# nanoscan.net
KiCad netlist of a schematic drawn in EAGLE
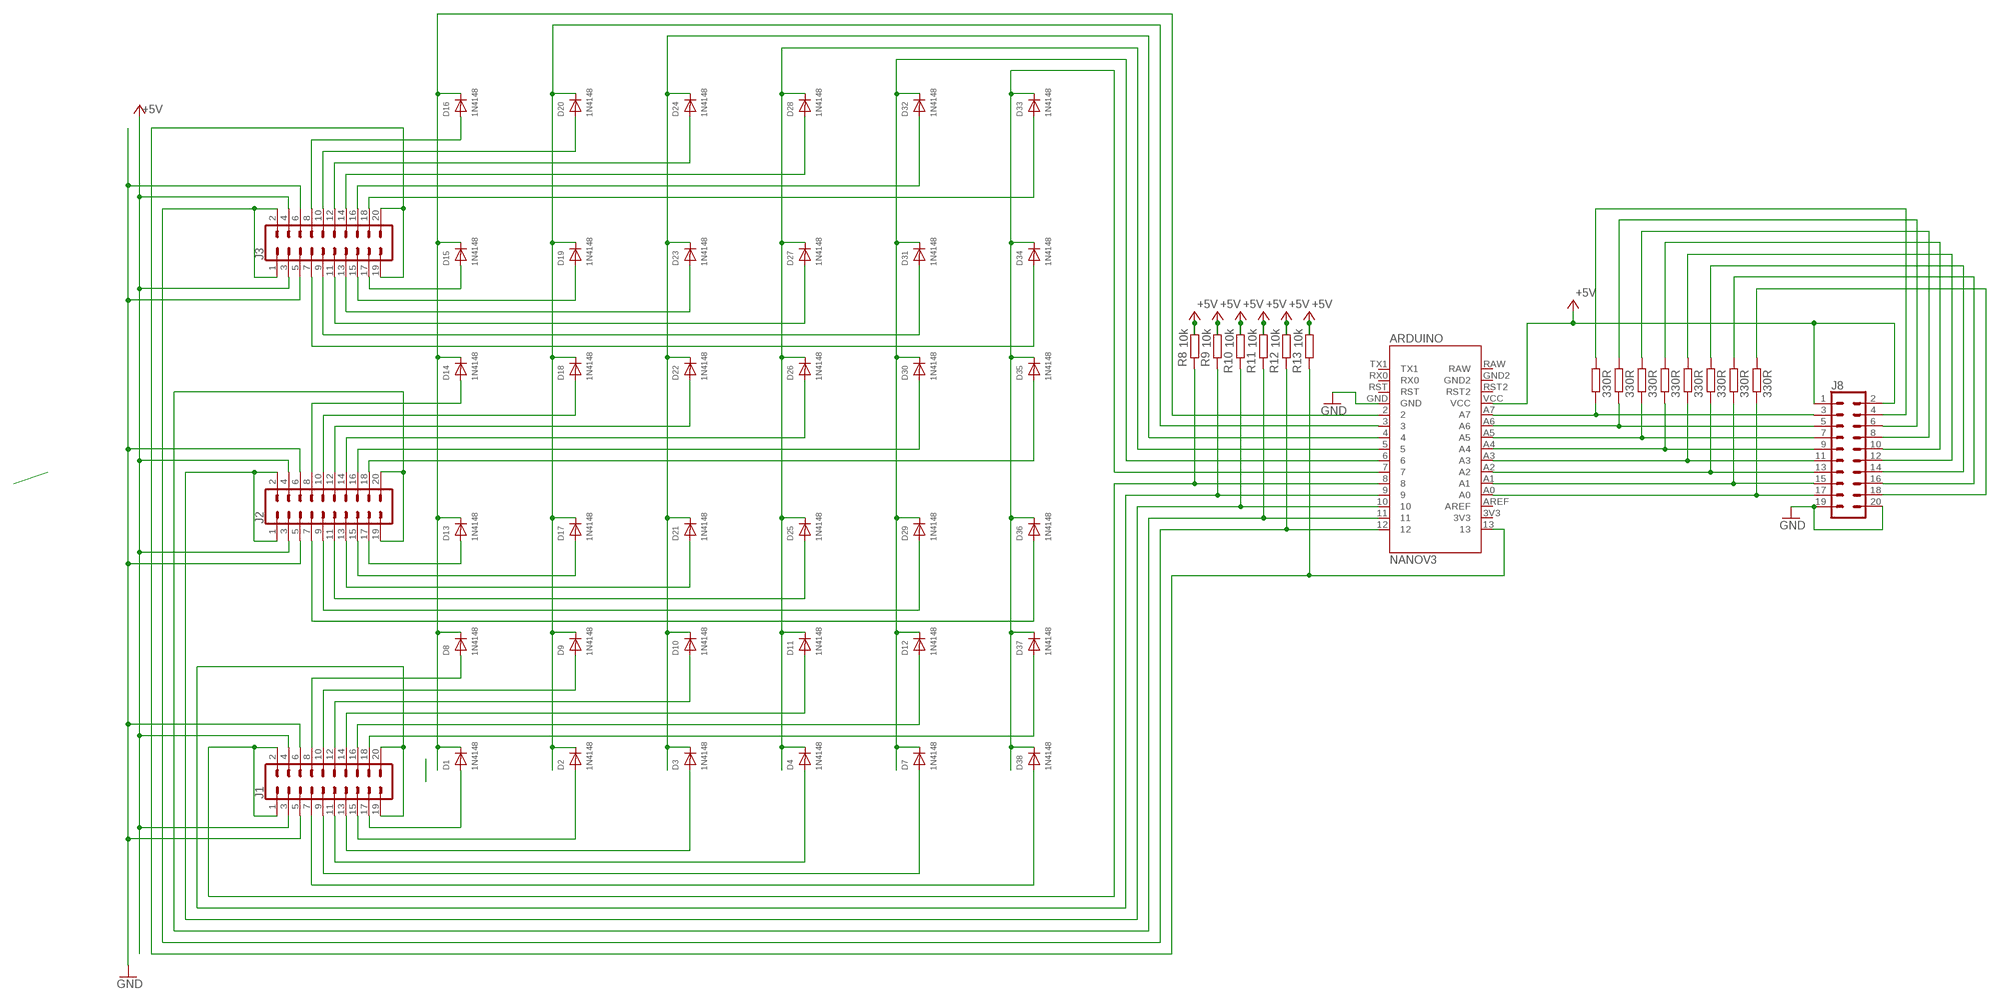
[diagram p0: schematic, sheet 1]

(export (version "E")
  (design (tool "Eeschema 10.0.6"))
  (components
    (comp (ref "ARDUINO")
      (value "NANOV3")
      (footprint "eagle-import:NANOV3")
      (libsource (lib "eagle-import") (part "NANOV3"))
    )
    (comp (ref "D1")
      (value "1N4148")
      (footprint "eagle-import:DO-1N4148")
      (libsource (lib "eagle-import") (part "DIODEDO-1N4148"))
    )
    (comp (ref "D2")
      (value "1N4148")
      (footprint "eagle-import:DO-1N4148")
      (libsource (lib "eagle-import") (part "DIODEDO-1N4148"))
    )
    (comp (ref "D3")
      (value "1N4148")
      (footprint "eagle-import:DO-1N4148")
      (libsource (lib "eagle-import") (part "DIODEDO-1N4148"))
    )
    (comp (ref "D4")
      (value "1N4148")
      (footprint "eagle-import:DO-1N4148")
      (libsource (lib "eagle-import") (part "DIODEDO-1N4148"))
    )
    (comp (ref "D7")
      (value "1N4148")
      (footprint "eagle-import:DO-1N4148")
      (libsource (lib "eagle-import") (part "DIODEDO-1N4148"))
    )
    (comp (ref "D8")
      (value "1N4148")
      (footprint "eagle-import:DO-1N4148")
      (libsource (lib "eagle-import") (part "DIODEDO-1N4148"))
    )
    (comp (ref "D9")
      (value "1N4148")
      (footprint "eagle-import:DO-1N4148")
      (libsource (lib "eagle-import") (part "DIODEDO-1N4148"))
    )
    (comp (ref "D10")
      (value "1N4148")
      (footprint "eagle-import:DO-1N4148")
      (libsource (lib "eagle-import") (part "DIODEDO-1N4148"))
    )
    (comp (ref "D11")
      (value "1N4148")
      (footprint "eagle-import:DO-1N4148")
      (libsource (lib "eagle-import") (part "DIODEDO-1N4148"))
    )
    (comp (ref "D12")
      (value "1N4148")
      (footprint "eagle-import:DO-1N4148")
      (libsource (lib "eagle-import") (part "DIODEDO-1N4148"))
    )
    (comp (ref "D13")
      (value "1N4148")
      (footprint "eagle-import:DO-1N4148")
      (libsource (lib "eagle-import") (part "DIODEDO-1N4148"))
    )
    (comp (ref "D14")
      (value "1N4148")
      (footprint "eagle-import:DO-1N4148")
      (libsource (lib "eagle-import") (part "DIODEDO-1N4148"))
    )
    (comp (ref "D15")
      (value "1N4148")
      (footprint "eagle-import:DO-1N4148")
      (libsource (lib "eagle-import") (part "DIODEDO-1N4148"))
    )
    (comp (ref "D16")
      (value "1N4148")
      (footprint "eagle-import:DO-1N4148")
      (libsource (lib "eagle-import") (part "DIODEDO-1N4148"))
    )
    (comp (ref "D17")
      (value "1N4148")
      (footprint "eagle-import:DO-1N4148")
      (libsource (lib "eagle-import") (part "DIODEDO-1N4148"))
    )
    (comp (ref "D18")
      (value "1N4148")
      (footprint "eagle-import:DO-1N4148")
      (libsource (lib "eagle-import") (part "DIODEDO-1N4148"))
    )
    (comp (ref "D19")
      (value "1N4148")
      (footprint "eagle-import:DO-1N4148")
      (libsource (lib "eagle-import") (part "DIODEDO-1N4148"))
    )
    (comp (ref "D20")
      (value "1N4148")
      (footprint "eagle-import:DO-1N4148")
      (libsource (lib "eagle-import") (part "DIODEDO-1N4148"))
    )
    (comp (ref "D21")
      (value "1N4148")
      (footprint "eagle-import:DO-1N4148")
      (libsource (lib "eagle-import") (part "DIODEDO-1N4148"))
    )
    (comp (ref "D22")
      (value "1N4148")
      (footprint "eagle-import:DO-1N4148")
      (libsource (lib "eagle-import") (part "DIODEDO-1N4148"))
    )
    (comp (ref "D23")
      (value "1N4148")
      (footprint "eagle-import:DO-1N4148")
      (libsource (lib "eagle-import") (part "DIODEDO-1N4148"))
    )
    (comp (ref "D24")
      (value "1N4148")
      (footprint "eagle-import:DO-1N4148")
      (libsource (lib "eagle-import") (part "DIODEDO-1N4148"))
    )
    (comp (ref "D25")
      (value "1N4148")
      (footprint "eagle-import:DO-1N4148")
      (libsource (lib "eagle-import") (part "DIODEDO-1N4148"))
    )
    (comp (ref "D26")
      (value "1N4148")
      (footprint "eagle-import:DO-1N4148")
      (libsource (lib "eagle-import") (part "DIODEDO-1N4148"))
    )
    (comp (ref "D27")
      (value "1N4148")
      (footprint "eagle-import:DO-1N4148")
      (libsource (lib "eagle-import") (part "DIODEDO-1N4148"))
    )
    (comp (ref "D28")
      (value "1N4148")
      (footprint "eagle-import:DO-1N4148")
      (libsource (lib "eagle-import") (part "DIODEDO-1N4148"))
    )
    (comp (ref "D29")
      (value "1N4148")
      (footprint "eagle-import:DO-1N4148")
      (libsource (lib "eagle-import") (part "DIODEDO-1N4148"))
    )
    (comp (ref "D30")
      (value "1N4148")
      (footprint "eagle-import:DO-1N4148")
      (libsource (lib "eagle-import") (part "DIODEDO-1N4148"))
    )
    (comp (ref "D31")
      (value "1N4148")
      (footprint "eagle-import:DO-1N4148")
      (libsource (lib "eagle-import") (part "DIODEDO-1N4148"))
    )
    (comp (ref "D32")
      (value "1N4148")
      (footprint "eagle-import:DO-1N4148")
      (libsource (lib "eagle-import") (part "DIODEDO-1N4148"))
    )
    (comp (ref "D33")
      (value "1N4148")
      (footprint "eagle-import:DO-1N4148")
      (libsource (lib "eagle-import") (part "DIODEDO-1N4148"))
    )
    (comp (ref "D34")
      (value "1N4148")
      (footprint "eagle-import:DO-1N4148")
      (libsource (lib "eagle-import") (part "DIODEDO-1N4148"))
    )
    (comp (ref "D35")
      (value "1N4148")
      (footprint "eagle-import:DO-1N4148")
      (libsource (lib "eagle-import") (part "DIODEDO-1N4148"))
    )
    (comp (ref "D36")
      (value "1N4148")
      (footprint "eagle-import:DO-1N4148")
      (libsource (lib "eagle-import") (part "DIODEDO-1N4148"))
    )
    (comp (ref "D37")
      (value "1N4148")
      (footprint "eagle-import:DO-1N4148")
      (libsource (lib "eagle-import") (part "DIODEDO-1N4148"))
    )
    (comp (ref "D38")
      (value "1N4148")
      (footprint "eagle-import:DO-1N4148")
      (libsource (lib "eagle-import") (part "DIODEDO-1N4148"))
    )
    (comp (ref "J1")
      (value "CONN_10X2SPECIAL")
      (footprint "eagle-import:2X10_LOCK_SPECIAL")
      (libsource (lib "eagle-import") (part "CONN_10X2SPECIAL"))
    )
    (comp (ref "J2")
      (value "CONN_10X2SPECIAL")
      (footprint "eagle-import:2X10_LOCK_SPECIAL")
      (libsource (lib "eagle-import") (part "CONN_10X2SPECIAL"))
    )
    (comp (ref "J3")
      (value "CONN_10X2SPECIAL")
      (footprint "eagle-import:2X10_LOCK_SPECIAL")
      (libsource (lib "eagle-import") (part "CONN_10X2SPECIAL"))
    )
    (comp (ref "J8")
      (value "CONN_10X2SPECIAL")
      (footprint "eagle-import:2X10_LOCK_SPECIAL")
      (libsource (lib "eagle-import") (part "CONN_10X2SPECIAL"))
    )
    (comp (ref "R0")
      (value "330R")
      (footprint "eagle-import:0207_10")
      (libsource (lib "eagle-import") (part "R-EU_0207/10"))
    )
    (comp (ref "R1")
      (value "330R")
      (footprint "eagle-import:0207_10")
      (libsource (lib "eagle-import") (part "R-EU_0207/10"))
    )
    (comp (ref "R2")
      (value "330R")
      (footprint "eagle-import:0207_10")
      (libsource (lib "eagle-import") (part "R-EU_0207/10"))
    )
    (comp (ref "R3")
      (value "330R")
      (footprint "eagle-import:0207_10")
      (libsource (lib "eagle-import") (part "R-EU_0207/10"))
    )
    (comp (ref "R4")
      (value "330R")
      (footprint "eagle-import:0207_10")
      (libsource (lib "eagle-import") (part "R-EU_0207/10"))
    )
    (comp (ref "R5")
      (value "330R")
      (footprint "eagle-import:0207_10")
      (libsource (lib "eagle-import") (part "R-EU_0207/10"))
    )
    (comp (ref "R6")
      (value "330R")
      (footprint "eagle-import:0207_10")
      (libsource (lib "eagle-import") (part "R-EU_0207/10"))
    )
    (comp (ref "R7")
      (value "330R")
      (footprint "eagle-import:0207_10")
      (libsource (lib "eagle-import") (part "R-EU_0207/10"))
    )
    (comp (ref "R8")
      (value "10k")
      (footprint "eagle-import:0207_10")
      (libsource (lib "eagle-import") (part "R-EU_0207/10"))
    )
    (comp (ref "R9")
      (value "10k")
      (footprint "eagle-import:0207_10")
      (libsource (lib "eagle-import") (part "R-EU_0207/10"))
    )
    (comp (ref "R10")
      (value "10k")
      (footprint "eagle-import:0207_10")
      (libsource (lib "eagle-import") (part "R-EU_0207/10"))
    )
    (comp (ref "R11")
      (value "10k")
      (footprint "eagle-import:0207_10")
      (libsource (lib "eagle-import") (part "R-EU_0207/10"))
    )
    (comp (ref "R12")
      (value "10k")
      (footprint "eagle-import:0207_10")
      (libsource (lib "eagle-import") (part "R-EU_0207/10"))
    )
    (comp (ref "R13")
      (value "10k")
      (footprint "eagle-import:0207_10")
      (libsource (lib "eagle-import") (part "R-EU_0207/10"))
    )
  )
  (nets
    (net (code "1") (name "+5V") (class "Default")
      (node (ref "ARDUINO") (pin "VCC") (pinfunction "VCC_VCC") (pintype "bidirectional"))
      (node (ref "J1") (pin "3") (pinfunction "3_3") (pintype "passive"))
      (node (ref "J1") (pin "4") (pinfunction "4_4") (pintype "passive"))
      (node (ref "J2") (pin "3") (pinfunction "3_3") (pintype "passive"))
      (node (ref "J2") (pin "4") (pinfunction "4_4") (pintype "passive"))
      (node (ref "J3") (pin "3") (pinfunction "3_3") (pintype "passive"))
      (node (ref "J3") (pin "4") (pinfunction "4_4") (pintype "passive"))
      (node (ref "J8") (pin "1") (pinfunction "1_1") (pintype "passive"))
      (node (ref "J8") (pin "2") (pinfunction "2_2") (pintype "passive"))
      (node (ref "R10") (pin "1") (pinfunction "1_1") (pintype "passive"))
      (node (ref "R11") (pin "1") (pinfunction "1_1") (pintype "passive"))
      (node (ref "R12") (pin "1") (pinfunction "1_1") (pintype "passive"))
      (node (ref "R13") (pin "1") (pinfunction "1_1") (pintype "passive"))
      (node (ref "R8") (pin "1") (pinfunction "1_1") (pintype "passive"))
      (node (ref "R9") (pin "1") (pinfunction "1_1") (pintype "passive"))
    )
    (net (code "2") (name "GND") (class "Default")
      (node (ref "ARDUINO") (pin "GND") (pinfunction "GND_GND") (pintype "bidirectional"))
      (node (ref "J1") (pin "5") (pinfunction "5_5") (pintype "passive"))
      (node (ref "J1") (pin "6") (pinfunction "6_6") (pintype "passive"))
      (node (ref "J2") (pin "5") (pinfunction "5_5") (pintype "passive"))
      (node (ref "J2") (pin "6") (pinfunction "6_6") (pintype "passive"))
      (node (ref "J3") (pin "5") (pinfunction "5_5") (pintype "passive"))
      (node (ref "J3") (pin "6") (pinfunction "6_6") (pintype "passive"))
      (node (ref "J8") (pin "19") (pinfunction "19_19") (pintype "passive"))
      (node (ref "J8") (pin "20") (pinfunction "20_20") (pintype "passive"))
    )
    (net (code "3") (name "Net-(ARDUINO-Pad2)") (class "Default")
      (node (ref "ARDUINO") (pin "2") (pinfunction "2_2") (pintype "bidirectional"))
      (node (ref "D1") (pin "C") (pinfunction "C_C") (pintype "passive"))
      (node (ref "D13") (pin "C") (pinfunction "C_C") (pintype "passive"))
      (node (ref "D14") (pin "C") (pinfunction "C_C") (pintype "passive"))
      (node (ref "D15") (pin "C") (pinfunction "C_C") (pintype "passive"))
      (node (ref "D16") (pin "C") (pinfunction "C_C") (pintype "passive"))
      (node (ref "D8") (pin "C") (pinfunction "C_C") (pintype "passive"))
    )
    (net (code "4") (name "Net-(ARDUINO-Pad3)") (class "Default")
      (node (ref "ARDUINO") (pin "3") (pinfunction "3_3") (pintype "bidirectional"))
      (node (ref "D17") (pin "C") (pinfunction "C_C") (pintype "passive"))
      (node (ref "D18") (pin "C") (pinfunction "C_C") (pintype "passive"))
      (node (ref "D19") (pin "C") (pinfunction "C_C") (pintype "passive"))
      (node (ref "D2") (pin "C") (pinfunction "C_C") (pintype "passive"))
      (node (ref "D20") (pin "C") (pinfunction "C_C") (pintype "passive"))
      (node (ref "D9") (pin "C") (pinfunction "C_C") (pintype "passive"))
    )
    (net (code "5") (name "Net-(ARDUINO-Pad4)") (class "Default")
      (node (ref "ARDUINO") (pin "4") (pinfunction "4_4") (pintype "bidirectional"))
      (node (ref "D10") (pin "C") (pinfunction "C_C") (pintype "passive"))
      (node (ref "D21") (pin "C") (pinfunction "C_C") (pintype "passive"))
      (node (ref "D22") (pin "C") (pinfunction "C_C") (pintype "passive"))
      (node (ref "D23") (pin "C") (pinfunction "C_C") (pintype "passive"))
      (node (ref "D24") (pin "C") (pinfunction "C_C") (pintype "passive"))
      (node (ref "D3") (pin "C") (pinfunction "C_C") (pintype "passive"))
    )
    (net (code "6") (name "Net-(ARDUINO-Pad5)") (class "Default")
      (node (ref "ARDUINO") (pin "5") (pinfunction "5_5") (pintype "bidirectional"))
      (node (ref "D11") (pin "C") (pinfunction "C_C") (pintype "passive"))
      (node (ref "D25") (pin "C") (pinfunction "C_C") (pintype "passive"))
      (node (ref "D26") (pin "C") (pinfunction "C_C") (pintype "passive"))
      (node (ref "D27") (pin "C") (pinfunction "C_C") (pintype "passive"))
      (node (ref "D28") (pin "C") (pinfunction "C_C") (pintype "passive"))
      (node (ref "D4") (pin "C") (pinfunction "C_C") (pintype "passive"))
    )
    (net (code "7") (name "Net-(ARDUINO-Pad6)") (class "Default")
      (node (ref "ARDUINO") (pin "6") (pinfunction "6_6") (pintype "bidirectional"))
      (node (ref "D12") (pin "C") (pinfunction "C_C") (pintype "passive"))
      (node (ref "D29") (pin "C") (pinfunction "C_C") (pintype "passive"))
      (node (ref "D30") (pin "C") (pinfunction "C_C") (pintype "passive"))
      (node (ref "D31") (pin "C") (pinfunction "C_C") (pintype "passive"))
      (node (ref "D32") (pin "C") (pinfunction "C_C") (pintype "passive"))
      (node (ref "D7") (pin "C") (pinfunction "C_C") (pintype "passive"))
    )
    (net (code "8") (name "Net-(ARDUINO-Pad7)") (class "Default")
      (node (ref "ARDUINO") (pin "7") (pinfunction "7_7") (pintype "bidirectional"))
      (node (ref "D33") (pin "C") (pinfunction "C_C") (pintype "passive"))
      (node (ref "D34") (pin "C") (pinfunction "C_C") (pintype "passive"))
      (node (ref "D35") (pin "C") (pinfunction "C_C") (pintype "passive"))
      (node (ref "D36") (pin "C") (pinfunction "C_C") (pintype "passive"))
      (node (ref "D37") (pin "C") (pinfunction "C_C") (pintype "passive"))
      (node (ref "D38") (pin "C") (pinfunction "C_C") (pintype "passive"))
    )
    (net (code "9") (name "Net-(ARDUINO-Pad8)") (class "Default")
      (node (ref "ARDUINO") (pin "8") (pinfunction "8_8") (pintype "bidirectional"))
      (node (ref "J1") (pin "1") (pinfunction "1_1") (pintype "passive"))
      (node (ref "J1") (pin "2") (pinfunction "2_2") (pintype "passive"))
      (node (ref "R8") (pin "2") (pinfunction "2_2") (pintype "passive"))
    )
    (net (code "10") (name "Net-(ARDUINO-Pad9)") (class "Default")
      (node (ref "ARDUINO") (pin "9") (pinfunction "9_9") (pintype "bidirectional"))
      (node (ref "J1") (pin "19") (pinfunction "19_19") (pintype "passive"))
      (node (ref "J1") (pin "20") (pinfunction "20_20") (pintype "passive"))
      (node (ref "R9") (pin "2") (pinfunction "2_2") (pintype "passive"))
    )
    (net (code "11") (name "Net-(ARDUINO-Pad10)") (class "Default")
      (node (ref "ARDUINO") (pin "10") (pinfunction "10_10") (pintype "bidirectional"))
      (node (ref "J2") (pin "1") (pinfunction "1_1") (pintype "passive"))
      (node (ref "J2") (pin "2") (pinfunction "2_2") (pintype "passive"))
      (node (ref "R10") (pin "2") (pinfunction "2_2") (pintype "passive"))
    )
    (net (code "12") (name "Net-(ARDUINO-Pad11)") (class "Default")
      (node (ref "ARDUINO") (pin "11") (pinfunction "11_11") (pintype "bidirectional"))
      (node (ref "J2") (pin "19") (pinfunction "19_19") (pintype "passive"))
      (node (ref "J2") (pin "20") (pinfunction "20_20") (pintype "passive"))
      (node (ref "R11") (pin "2") (pinfunction "2_2") (pintype "passive"))
    )
    (net (code "13") (name "Net-(ARDUINO-Pad12)") (class "Default")
      (node (ref "ARDUINO") (pin "12") (pinfunction "12_12") (pintype "bidirectional"))
      (node (ref "J3") (pin "1") (pinfunction "1_1") (pintype "passive"))
      (node (ref "J3") (pin "2") (pinfunction "2_2") (pintype "passive"))
      (node (ref "R12") (pin "2") (pinfunction "2_2") (pintype "passive"))
    )
    (net (code "14") (name "Net-(ARDUINO-Pad13)") (class "Default")
      (node (ref "ARDUINO") (pin "13") (pinfunction "13_13") (pintype "bidirectional"))
      (node (ref "J3") (pin "19") (pinfunction "19_19") (pintype "passive"))
      (node (ref "J3") (pin "20") (pinfunction "20_20") (pintype "passive"))
      (node (ref "R13") (pin "2") (pinfunction "2_2") (pintype "passive"))
    )
    (net (code "15") (name "Net-(ARDUINO-PadA0)") (class "Default")
      (node (ref "ARDUINO") (pin "A0") (pinfunction "A0_A0") (pintype "bidirectional"))
      (node (ref "J8") (pin "17") (pinfunction "17_17") (pintype "passive"))
      (node (ref "R0") (pin "1") (pinfunction "1_1") (pintype "passive"))
    )
    (net (code "16") (name "Net-(ARDUINO-PadA1)") (class "Default")
      (node (ref "ARDUINO") (pin "A1") (pinfunction "A1_A1") (pintype "bidirectional"))
      (node (ref "J8") (pin "15") (pinfunction "15_15") (pintype "passive"))
      (node (ref "R1") (pin "1") (pinfunction "1_1") (pintype "passive"))
    )
    (net (code "17") (name "Net-(ARDUINO-PadA2)") (class "Default")
      (node (ref "ARDUINO") (pin "A2") (pinfunction "A2_A2") (pintype "bidirectional"))
      (node (ref "J8") (pin "13") (pinfunction "13_13") (pintype "passive"))
      (node (ref "R2") (pin "1") (pinfunction "1_1") (pintype "passive"))
    )
    (net (code "18") (name "Net-(ARDUINO-PadA3)") (class "Default")
      (node (ref "ARDUINO") (pin "A3") (pinfunction "A3_A3") (pintype "bidirectional"))
      (node (ref "J8") (pin "11") (pinfunction "11_11") (pintype "passive"))
      (node (ref "R3") (pin "1") (pinfunction "1_1") (pintype "passive"))
    )
    (net (code "19") (name "Net-(ARDUINO-PadA4)") (class "Default")
      (node (ref "ARDUINO") (pin "A4") (pinfunction "A4_A4") (pintype "bidirectional"))
      (node (ref "J8") (pin "9") (pinfunction "9_9") (pintype "passive"))
      (node (ref "R4") (pin "1") (pinfunction "1_1") (pintype "passive"))
    )
    (net (code "20") (name "Net-(ARDUINO-PadA5)") (class "Default")
      (node (ref "ARDUINO") (pin "A5") (pinfunction "A5_A5") (pintype "bidirectional"))
      (node (ref "J8") (pin "7") (pinfunction "7_7") (pintype "passive"))
      (node (ref "R5") (pin "1") (pinfunction "1_1") (pintype "passive"))
    )
    (net (code "21") (name "Net-(ARDUINO-PadA6)") (class "Default")
      (node (ref "ARDUINO") (pin "A6") (pinfunction "A6_A6") (pintype "bidirectional"))
      (node (ref "J8") (pin "5") (pinfunction "5_5") (pintype "passive"))
      (node (ref "R6") (pin "1") (pinfunction "1_1") (pintype "passive"))
    )
    (net (code "22") (name "Net-(ARDUINO-PadA7)") (class "Default")
      (node (ref "ARDUINO") (pin "A7") (pinfunction "A7_A7") (pintype "bidirectional"))
      (node (ref "J8") (pin "3") (pinfunction "3_3") (pintype "passive"))
      (node (ref "R7") (pin "1") (pinfunction "1_1") (pintype "passive"))
    )
    (net (code "23") (name "Net-(D1-PadA)") (class "Default")
      (node (ref "D1") (pin "A") (pinfunction "A_A") (pintype "passive"))
      (node (ref "J1") (pin "17") (pinfunction "17_17") (pintype "passive"))
    )
    (net (code "24") (name "Net-(D2-PadA)") (class "Default")
      (node (ref "D2") (pin "A") (pinfunction "A_A") (pintype "passive"))
      (node (ref "J1") (pin "15") (pinfunction "15_15") (pintype "passive"))
    )
    (net (code "25") (name "Net-(D3-PadA)") (class "Default")
      (node (ref "D3") (pin "A") (pinfunction "A_A") (pintype "passive"))
      (node (ref "J1") (pin "13") (pinfunction "13_13") (pintype "passive"))
    )
    (net (code "26") (name "Net-(D4-PadA)") (class "Default")
      (node (ref "D4") (pin "A") (pinfunction "A_A") (pintype "passive"))
      (node (ref "J1") (pin "11") (pinfunction "11_11") (pintype "passive"))
    )
    (net (code "27") (name "Net-(D7-PadA)") (class "Default")
      (node (ref "D7") (pin "A") (pinfunction "A_A") (pintype "passive"))
      (node (ref "J1") (pin "9") (pinfunction "9_9") (pintype "passive"))
    )
    (net (code "28") (name "Net-(D8-PadA)") (class "Default")
      (node (ref "D8") (pin "A") (pinfunction "A_A") (pintype "passive"))
      (node (ref "J1") (pin "8") (pinfunction "8_8") (pintype "passive"))
    )
    (net (code "29") (name "Net-(D9-PadA)") (class "Default")
      (node (ref "D9") (pin "A") (pinfunction "A_A") (pintype "passive"))
      (node (ref "J1") (pin "10") (pinfunction "10_10") (pintype "passive"))
    )
    (net (code "30") (name "Net-(D10-PadA)") (class "Default")
      (node (ref "D10") (pin "A") (pinfunction "A_A") (pintype "passive"))
      (node (ref "J1") (pin "12") (pinfunction "12_12") (pintype "passive"))
    )
    (net (code "31") (name "Net-(D11-PadA)") (class "Default")
      (node (ref "D11") (pin "A") (pinfunction "A_A") (pintype "passive"))
      (node (ref "J1") (pin "14") (pinfunction "14_14") (pintype "passive"))
    )
    (net (code "32") (name "Net-(D12-PadA)") (class "Default")
      (node (ref "D12") (pin "A") (pinfunction "A_A") (pintype "passive"))
      (node (ref "J1") (pin "16") (pinfunction "16_16") (pintype "passive"))
    )
    (net (code "33") (name "Net-(D13-PadA)") (class "Default")
      (node (ref "D13") (pin "A") (pinfunction "A_A") (pintype "passive"))
      (node (ref "J2") (pin "17") (pinfunction "17_17") (pintype "passive"))
    )
    (net (code "34") (name "Net-(D14-PadA)") (class "Default")
      (node (ref "D14") (pin "A") (pinfunction "A_A") (pintype "passive"))
      (node (ref "J2") (pin "8") (pinfunction "8_8") (pintype "passive"))
    )
    (net (code "35") (name "Net-(D15-PadA)") (class "Default")
      (node (ref "D15") (pin "A") (pinfunction "A_A") (pintype "passive"))
      (node (ref "J3") (pin "17") (pinfunction "17_17") (pintype "passive"))
    )
    (net (code "36") (name "Net-(D16-PadA)") (class "Default")
      (node (ref "D16") (pin "A") (pinfunction "A_A") (pintype "passive"))
      (node (ref "J3") (pin "8") (pinfunction "8_8") (pintype "passive"))
    )
    (net (code "37") (name "Net-(D17-PadA)") (class "Default")
      (node (ref "D17") (pin "A") (pinfunction "A_A") (pintype "passive"))
      (node (ref "J2") (pin "15") (pinfunction "15_15") (pintype "passive"))
    )
    (net (code "38") (name "Net-(D18-PadA)") (class "Default")
      (node (ref "D18") (pin "A") (pinfunction "A_A") (pintype "passive"))
      (node (ref "J2") (pin "10") (pinfunction "10_10") (pintype "passive"))
    )
    (net (code "39") (name "Net-(D19-PadA)") (class "Default")
      (node (ref "D19") (pin "A") (pinfunction "A_A") (pintype "passive"))
      (node (ref "J3") (pin "15") (pinfunction "15_15") (pintype "passive"))
    )
    (net (code "40") (name "Net-(D20-PadA)") (class "Default")
      (node (ref "D20") (pin "A") (pinfunction "A_A") (pintype "passive"))
      (node (ref "J3") (pin "10") (pinfunction "10_10") (pintype "passive"))
    )
    (net (code "41") (name "Net-(D21-PadA)") (class "Default")
      (node (ref "D21") (pin "A") (pinfunction "A_A") (pintype "passive"))
      (node (ref "J2") (pin "13") (pinfunction "13_13") (pintype "passive"))
    )
    (net (code "42") (name "Net-(D22-PadA)") (class "Default")
      (node (ref "D22") (pin "A") (pinfunction "A_A") (pintype "passive"))
      (node (ref "J2") (pin "12") (pinfunction "12_12") (pintype "passive"))
    )
    (net (code "43") (name "Net-(D23-PadA)") (class "Default")
      (node (ref "D23") (pin "A") (pinfunction "A_A") (pintype "passive"))
      (node (ref "J3") (pin "13") (pinfunction "13_13") (pintype "passive"))
    )
    (net (code "44") (name "Net-(D24-PadA)") (class "Default")
      (node (ref "D24") (pin "A") (pinfunction "A_A") (pintype "passive"))
      (node (ref "J3") (pin "12") (pinfunction "12_12") (pintype "passive"))
    )
    (net (code "45") (name "Net-(D25-PadA)") (class "Default")
      (node (ref "D25") (pin "A") (pinfunction "A_A") (pintype "passive"))
      (node (ref "J2") (pin "11") (pinfunction "11_11") (pintype "passive"))
    )
    (net (code "46") (name "Net-(D26-PadA)") (class "Default")
      (node (ref "D26") (pin "A") (pinfunction "A_A") (pintype "passive"))
      (node (ref "J2") (pin "14") (pinfunction "14_14") (pintype "passive"))
    )
    (net (code "47") (name "Net-(D27-PadA)") (class "Default")
      (node (ref "D27") (pin "A") (pinfunction "A_A") (pintype "passive"))
      (node (ref "J3") (pin "11") (pinfunction "11_11") (pintype "passive"))
    )
    (net (code "48") (name "Net-(D28-PadA)") (class "Default")
      (node (ref "D28") (pin "A") (pinfunction "A_A") (pintype "passive"))
      (node (ref "J3") (pin "14") (pinfunction "14_14") (pintype "passive"))
    )
    (net (code "49") (name "Net-(D29-PadA)") (class "Default")
      (node (ref "D29") (pin "A") (pinfunction "A_A") (pintype "passive"))
      (node (ref "J2") (pin "9") (pinfunction "9_9") (pintype "passive"))
    )
    (net (code "50") (name "Net-(D30-PadA)") (class "Default")
      (node (ref "D30") (pin "A") (pinfunction "A_A") (pintype "passive"))
      (node (ref "J2") (pin "16") (pinfunction "16_16") (pintype "passive"))
    )
    (net (code "51") (name "Net-(D31-PadA)") (class "Default")
      (node (ref "D31") (pin "A") (pinfunction "A_A") (pintype "passive"))
      (node (ref "J3") (pin "9") (pinfunction "9_9") (pintype "passive"))
    )
    (net (code "52") (name "Net-(D32-PadA)") (class "Default")
      (node (ref "D32") (pin "A") (pinfunction "A_A") (pintype "passive"))
      (node (ref "J3") (pin "16") (pinfunction "16_16") (pintype "passive"))
    )
    (net (code "53") (name "Net-(D33-PadA)") (class "Default")
      (node (ref "D33") (pin "A") (pinfunction "A_A") (pintype "passive"))
      (node (ref "J3") (pin "18") (pinfunction "18_18") (pintype "passive"))
    )
    (net (code "54") (name "Net-(D34-PadA)") (class "Default")
      (node (ref "D34") (pin "A") (pinfunction "A_A") (pintype "passive"))
      (node (ref "J3") (pin "7") (pinfunction "7_7") (pintype "passive"))
    )
    (net (code "55") (name "Net-(D35-PadA)") (class "Default")
      (node (ref "D35") (pin "A") (pinfunction "A_A") (pintype "passive"))
      (node (ref "J2") (pin "18") (pinfunction "18_18") (pintype "passive"))
    )
    (net (code "56") (name "Net-(D36-PadA)") (class "Default")
      (node (ref "D36") (pin "A") (pinfunction "A_A") (pintype "passive"))
      (node (ref "J2") (pin "7") (pinfunction "7_7") (pintype "passive"))
    )
    (net (code "57") (name "Net-(D37-PadA)") (class "Default")
      (node (ref "D37") (pin "A") (pinfunction "A_A") (pintype "passive"))
      (node (ref "J1") (pin "18") (pinfunction "18_18") (pintype "passive"))
    )
    (net (code "58") (name "Net-(D38-PadA)") (class "Default")
      (node (ref "D38") (pin "A") (pinfunction "A_A") (pintype "passive"))
      (node (ref "J1") (pin "7") (pinfunction "7_7") (pintype "passive"))
    )
    (net (code "59") (name "Net-(J8-Pad4)") (class "Default")
      (node (ref "J8") (pin "4") (pinfunction "4_4") (pintype "passive"))
      (node (ref "R7") (pin "2") (pinfunction "2_2") (pintype "passive"))
    )
    (net (code "60") (name "Net-(J8-Pad6)") (class "Default")
      (node (ref "J8") (pin "6") (pinfunction "6_6") (pintype "passive"))
      (node (ref "R6") (pin "2") (pinfunction "2_2") (pintype "passive"))
    )
    (net (code "61") (name "Net-(J8-Pad8)") (class "Default")
      (node (ref "J8") (pin "8") (pinfunction "8_8") (pintype "passive"))
      (node (ref "R5") (pin "2") (pinfunction "2_2") (pintype "passive"))
    )
    (net (code "62") (name "Net-(J8-Pad10)") (class "Default")
      (node (ref "J8") (pin "10") (pinfunction "10_10") (pintype "passive"))
      (node (ref "R4") (pin "2") (pinfunction "2_2") (pintype "passive"))
    )
    (net (code "63") (name "Net-(J8-Pad12)") (class "Default")
      (node (ref "J8") (pin "12") (pinfunction "12_12") (pintype "passive"))
      (node (ref "R3") (pin "2") (pinfunction "2_2") (pintype "passive"))
    )
    (net (code "64") (name "Net-(J8-Pad14)") (class "Default")
      (node (ref "J8") (pin "14") (pinfunction "14_14") (pintype "passive"))
      (node (ref "R2") (pin "2") (pinfunction "2_2") (pintype "passive"))
    )
    (net (code "65") (name "Net-(J8-Pad16)") (class "Default")
      (node (ref "J8") (pin "16") (pinfunction "16_16") (pintype "passive"))
      (node (ref "R1") (pin "2") (pinfunction "2_2") (pintype "passive"))
    )
    (net (code "66") (name "Net-(J8-Pad18)") (class "Default")
      (node (ref "J8") (pin "18") (pinfunction "18_18") (pintype "passive"))
      (node (ref "R0") (pin "2") (pinfunction "2_2") (pintype "passive"))
    )
    (net (code "67") (name "unconnected-(ARDUINO-Pad3V3)") (class "Default")
      (node (ref "ARDUINO") (pin "3V3") (pinfunction "3V3_3V3") (pintype "bidirectional"))
    )
    (net (code "68") (name "unconnected-(ARDUINO-PadAREF)") (class "Default")
      (node (ref "ARDUINO") (pin "AREF") (pinfunction "AREF_AREF") (pintype "bidirectional"))
    )
    (net (code "69") (name "unconnected-(ARDUINO-PadGND2)") (class "Default")
      (node (ref "ARDUINO") (pin "GND2") (pinfunction "GND2_GND2") (pintype "bidirectional"))
    )
    (net (code "70") (name "unconnected-(ARDUINO-PadRAW)") (class "Default")
      (node (ref "ARDUINO") (pin "RAW") (pinfunction "RAW_RAW") (pintype "bidirectional"))
    )
    (net (code "71") (name "unconnected-(ARDUINO-PadRST)") (class "Default")
      (node (ref "ARDUINO") (pin "RST") (pinfunction "RST_RST") (pintype "bidirectional"))
    )
    (net (code "72") (name "unconnected-(ARDUINO-PadRST2)") (class "Default")
      (node (ref "ARDUINO") (pin "RST2") (pinfunction "RST2_RST2") (pintype "bidirectional"))
    )
    (net (code "73") (name "unconnected-(ARDUINO-PadRX0)") (class "Default")
      (node (ref "ARDUINO") (pin "RX0") (pinfunction "RX0_RX0") (pintype "bidirectional"))
    )
    (net (code "74") (name "unconnected-(ARDUINO-PadTX1)") (class "Default")
      (node (ref "ARDUINO") (pin "TX1") (pinfunction "TX1_TX1") (pintype "bidirectional"))
    )
  )
)
